# VGA_Breakout_Board.net
KiCad netlist of a schematic drawn in EAGLE
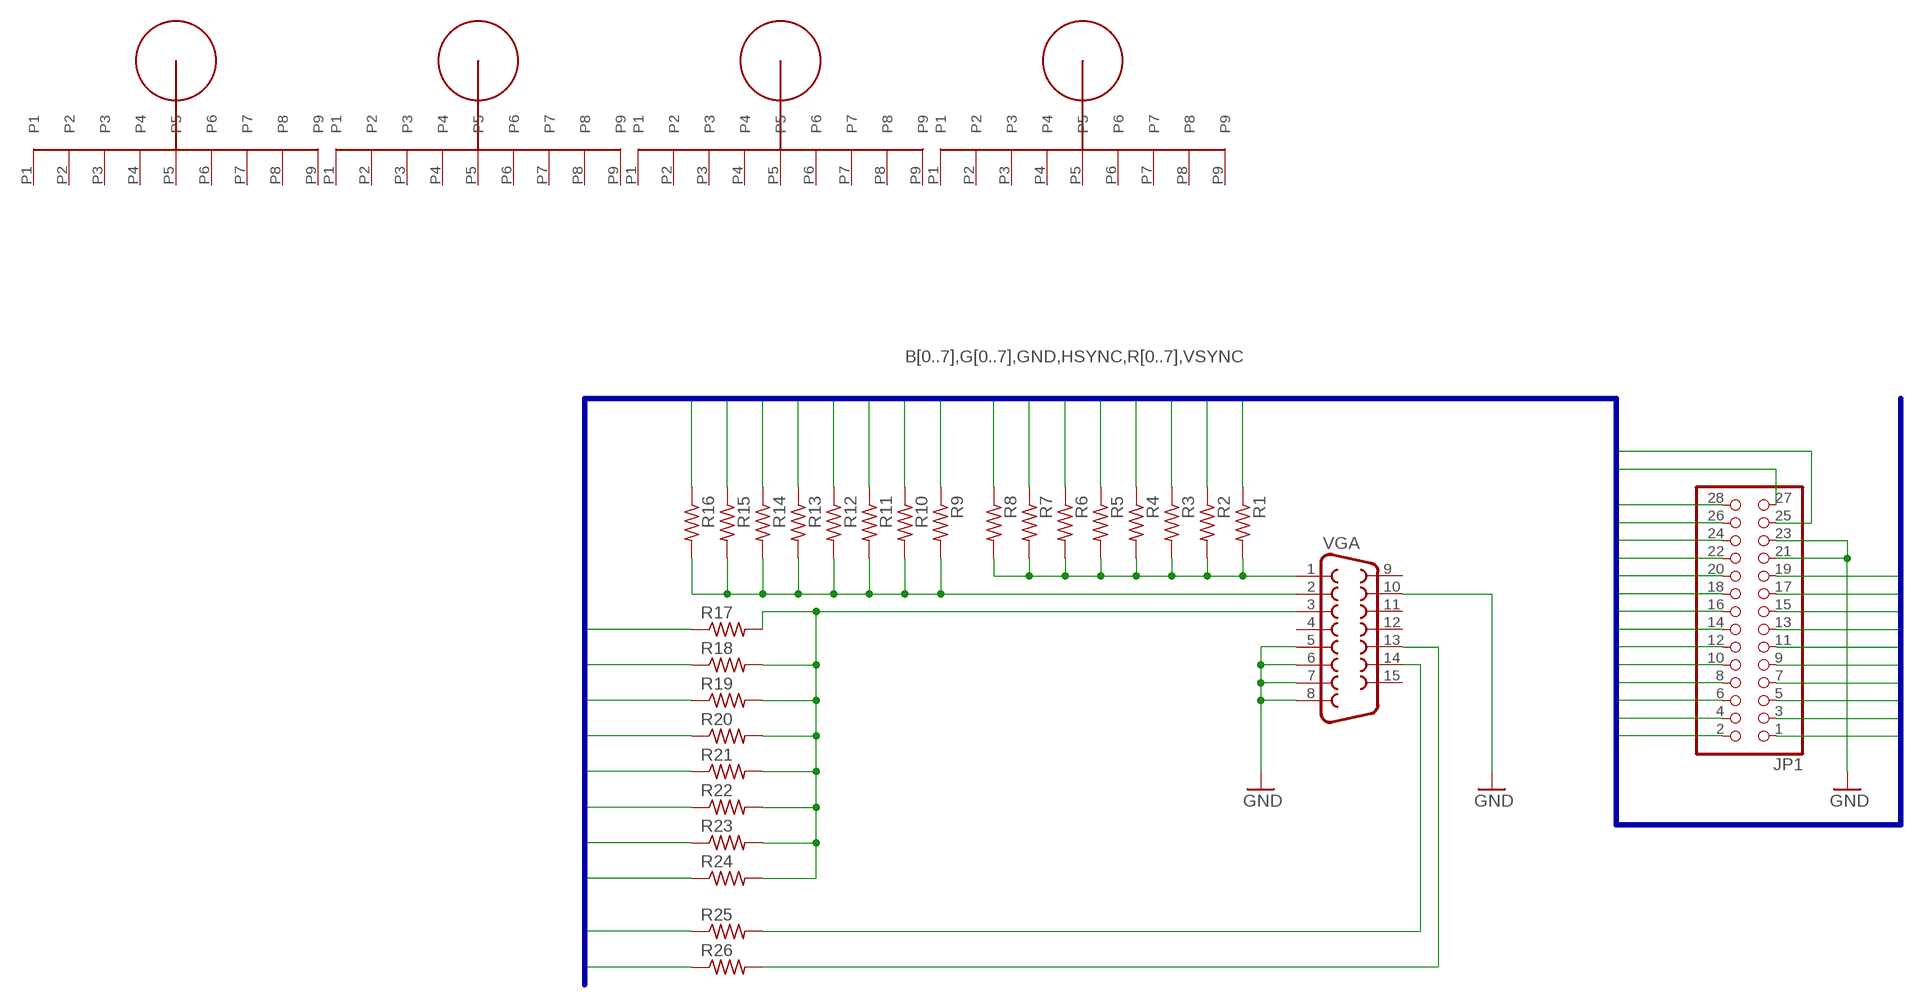
[diagram p0: schematic, sheet 1]

(export (version "E")
  (design (tool "Eeschema 10.0.6"))
  (components
    (comp (ref "JP1")
      (value "PINHD-2X14")
      (footprint "eagle-import:2X14")
      (libsource (lib "eagle-import") (part "PINHD-2X14"))
    )
    (comp (ref "R1")
      (value "R-US_0207/10")
      (footprint "eagle-import:0207_10")
      (libsource (lib "eagle-import") (part "R-US_0207/10"))
    )
    (comp (ref "R2")
      (value "R-US_0207/10")
      (footprint "eagle-import:0207_10")
      (libsource (lib "eagle-import") (part "R-US_0207/10"))
    )
    (comp (ref "R3")
      (value "R-US_0207/10")
      (footprint "eagle-import:0207_10")
      (libsource (lib "eagle-import") (part "R-US_0207/10"))
    )
    (comp (ref "R4")
      (value "R-US_0207/10")
      (footprint "eagle-import:0207_10")
      (libsource (lib "eagle-import") (part "R-US_0207/10"))
    )
    (comp (ref "R5")
      (value "R-US_0207/10")
      (footprint "eagle-import:0207_10")
      (libsource (lib "eagle-import") (part "R-US_0207/10"))
    )
    (comp (ref "R6")
      (value "R-US_0207/10")
      (footprint "eagle-import:0207_10")
      (libsource (lib "eagle-import") (part "R-US_0207/10"))
    )
    (comp (ref "R7")
      (value "R-US_0207/10")
      (footprint "eagle-import:0207_10")
      (libsource (lib "eagle-import") (part "R-US_0207/10"))
    )
    (comp (ref "R8")
      (value "R-US_0207/10")
      (footprint "eagle-import:0207_10")
      (libsource (lib "eagle-import") (part "R-US_0207/10"))
    )
    (comp (ref "R9")
      (value "R-US_0207/10")
      (footprint "eagle-import:0207_10")
      (libsource (lib "eagle-import") (part "R-US_0207/10"))
    )
    (comp (ref "R10")
      (value "R-US_0207/10")
      (footprint "eagle-import:0207_10")
      (libsource (lib "eagle-import") (part "R-US_0207/10"))
    )
    (comp (ref "R11")
      (value "R-US_0207/10")
      (footprint "eagle-import:0207_10")
      (libsource (lib "eagle-import") (part "R-US_0207/10"))
    )
    (comp (ref "R12")
      (value "R-US_0207/10")
      (footprint "eagle-import:0207_10")
      (libsource (lib "eagle-import") (part "R-US_0207/10"))
    )
    (comp (ref "R13")
      (value "R-US_0207/10")
      (footprint "eagle-import:0207_10")
      (libsource (lib "eagle-import") (part "R-US_0207/10"))
    )
    (comp (ref "R14")
      (value "R-US_0207/10")
      (footprint "eagle-import:0207_10")
      (libsource (lib "eagle-import") (part "R-US_0207/10"))
    )
    (comp (ref "R15")
      (value "R-US_0207/10")
      (footprint "eagle-import:0207_10")
      (libsource (lib "eagle-import") (part "R-US_0207/10"))
    )
    (comp (ref "R16")
      (value "R-US_0207/10")
      (footprint "eagle-import:0207_10")
      (libsource (lib "eagle-import") (part "R-US_0207/10"))
    )
    (comp (ref "R17")
      (value "R-US_0207/10")
      (footprint "eagle-import:0207_10")
      (libsource (lib "eagle-import") (part "R-US_0207/10"))
    )
    (comp (ref "R18")
      (value "R-US_0207/10")
      (footprint "eagle-import:0207_10")
      (libsource (lib "eagle-import") (part "R-US_0207/10"))
    )
    (comp (ref "R19")
      (value "R-US_0207/10")
      (footprint "eagle-import:0207_10")
      (libsource (lib "eagle-import") (part "R-US_0207/10"))
    )
    (comp (ref "R20")
      (value "R-US_0207/10")
      (footprint "eagle-import:0207_10")
      (libsource (lib "eagle-import") (part "R-US_0207/10"))
    )
    (comp (ref "R21")
      (value "R-US_0207/10")
      (footprint "eagle-import:0207_10")
      (libsource (lib "eagle-import") (part "R-US_0207/10"))
    )
    (comp (ref "R22")
      (value "R-US_0207/10")
      (footprint "eagle-import:0207_10")
      (libsource (lib "eagle-import") (part "R-US_0207/10"))
    )
    (comp (ref "R23")
      (value "R-US_0207/10")
      (footprint "eagle-import:0207_10")
      (libsource (lib "eagle-import") (part "R-US_0207/10"))
    )
    (comp (ref "R24")
      (value "R-US_0207/10")
      (footprint "eagle-import:0207_10")
      (libsource (lib "eagle-import") (part "R-US_0207/10"))
    )
    (comp (ref "R25")
      (value "R-US_0207/10")
      (footprint "eagle-import:0207_10")
      (libsource (lib "eagle-import") (part "R-US_0207/10"))
    )
    (comp (ref "R26")
      (value "R-US_0207/10")
      (footprint "eagle-import:0207_10")
      (libsource (lib "eagle-import") (part "R-US_0207/10"))
    )
    (comp (ref "U$1")
      (value "STANDOFF")
      (footprint "eagle-import:STANDOFF")
      (libsource (lib "eagle-import") (part "STANDOFF"))
    )
    (comp (ref "U$2")
      (value "STANDOFF")
      (footprint "eagle-import:STANDOFF")
      (libsource (lib "eagle-import") (part "STANDOFF"))
    )
    (comp (ref "U$3")
      (value "STANDOFF")
      (footprint "eagle-import:STANDOFF")
      (libsource (lib "eagle-import") (part "STANDOFF"))
    )
    (comp (ref "U$4")
      (value "STANDOFF")
      (footprint "eagle-import:STANDOFF")
      (libsource (lib "eagle-import") (part "STANDOFF"))
    )
    (comp (ref "VGA")
      (value "F15HDH")
      (footprint "eagle-import:HDF15H")
      (libsource (lib "eagle-import") (part "F15HDH"))
    )
  )
  (nets
    (net (code "1") (name "/B0") (class "Default")
      (node (ref "JP1") (pin "18") (pinfunction "18_18") (pintype "passive"))
      (node (ref "R17") (pin "1") (pinfunction "1_1") (pintype "passive"))
    )
    (net (code "2") (name "/B1") (class "Default")
      (node (ref "JP1") (pin "20") (pinfunction "20_20") (pintype "passive"))
      (node (ref "R18") (pin "1") (pinfunction "1_1") (pintype "passive"))
    )
    (net (code "3") (name "/B2") (class "Default")
      (node (ref "JP1") (pin "22") (pinfunction "22_22") (pintype "passive"))
      (node (ref "R19") (pin "1") (pinfunction "1_1") (pintype "passive"))
    )
    (net (code "4") (name "/B3") (class "Default")
      (node (ref "JP1") (pin "24") (pinfunction "24_24") (pintype "passive"))
      (node (ref "R20") (pin "1") (pinfunction "1_1") (pintype "passive"))
    )
    (net (code "5") (name "/B4") (class "Default")
      (node (ref "JP1") (pin "26") (pinfunction "26_26") (pintype "passive"))
      (node (ref "R21") (pin "1") (pinfunction "1_1") (pintype "passive"))
    )
    (net (code "6") (name "/B5") (class "Default")
      (node (ref "JP1") (pin "28") (pinfunction "28_28") (pintype "passive"))
      (node (ref "R22") (pin "1") (pinfunction "1_1") (pintype "passive"))
    )
    (net (code "7") (name "/B6") (class "Default")
      (node (ref "JP1") (pin "27") (pinfunction "27_27") (pintype "passive"))
      (node (ref "R23") (pin "1") (pinfunction "1_1") (pintype "passive"))
    )
    (net (code "8") (name "/B7") (class "Default")
      (node (ref "JP1") (pin "25") (pinfunction "25_25") (pintype "passive"))
      (node (ref "R24") (pin "1") (pinfunction "1_1") (pintype "passive"))
    )
    (net (code "9") (name "/G0") (class "Default")
      (node (ref "JP1") (pin "1") (pinfunction "1_1") (pintype "passive"))
      (node (ref "R9") (pin "1") (pinfunction "1_1") (pintype "passive"))
    )
    (net (code "10") (name "/G1") (class "Default")
      (node (ref "JP1") (pin "3") (pinfunction "3_3") (pintype "passive"))
      (node (ref "R10") (pin "1") (pinfunction "1_1") (pintype "passive"))
    )
    (net (code "11") (name "/G2") (class "Default")
      (node (ref "JP1") (pin "5") (pinfunction "5_5") (pintype "passive"))
      (node (ref "R11") (pin "1") (pinfunction "1_1") (pintype "passive"))
    )
    (net (code "12") (name "/G3") (class "Default")
      (node (ref "JP1") (pin "7") (pinfunction "7_7") (pintype "passive"))
      (node (ref "R12") (pin "1") (pinfunction "1_1") (pintype "passive"))
    )
    (net (code "13") (name "/G4") (class "Default")
      (node (ref "JP1") (pin "9") (pinfunction "9_9") (pintype "passive"))
      (node (ref "R13") (pin "1") (pinfunction "1_1") (pintype "passive"))
    )
    (net (code "14") (name "/G5") (class "Default")
      (node (ref "JP1") (pin "11") (pinfunction "11_11") (pintype "passive"))
      (node (ref "R14") (pin "1") (pinfunction "1_1") (pintype "passive"))
    )
    (net (code "15") (name "/G6") (class "Default")
      (node (ref "JP1") (pin "13") (pinfunction "13_13") (pintype "passive"))
      (node (ref "R15") (pin "1") (pinfunction "1_1") (pintype "passive"))
    )
    (net (code "16") (name "/G7") (class "Default")
      (node (ref "JP1") (pin "15") (pinfunction "15_15") (pintype "passive"))
      (node (ref "R16") (pin "1") (pinfunction "1_1") (pintype "passive"))
    )
    (net (code "17") (name "/HSYNC") (class "Default")
      (node (ref "JP1") (pin "17") (pinfunction "17_17") (pintype "passive"))
      (node (ref "R26") (pin "1") (pinfunction "1_1") (pintype "passive"))
    )
    (net (code "18") (name "/R0") (class "Default")
      (node (ref "JP1") (pin "16") (pinfunction "16_16") (pintype "passive"))
      (node (ref "R1") (pin "1") (pinfunction "1_1") (pintype "passive"))
    )
    (net (code "19") (name "/R1") (class "Default")
      (node (ref "JP1") (pin "14") (pinfunction "14_14") (pintype "passive"))
      (node (ref "R2") (pin "1") (pinfunction "1_1") (pintype "passive"))
    )
    (net (code "20") (name "/R2") (class "Default")
      (node (ref "JP1") (pin "12") (pinfunction "12_12") (pintype "passive"))
      (node (ref "R3") (pin "1") (pinfunction "1_1") (pintype "passive"))
    )
    (net (code "21") (name "/R3") (class "Default")
      (node (ref "JP1") (pin "10") (pinfunction "10_10") (pintype "passive"))
      (node (ref "R4") (pin "1") (pinfunction "1_1") (pintype "passive"))
    )
    (net (code "22") (name "/R4") (class "Default")
      (node (ref "JP1") (pin "8") (pinfunction "8_8") (pintype "passive"))
      (node (ref "R5") (pin "1") (pinfunction "1_1") (pintype "passive"))
    )
    (net (code "23") (name "/R5") (class "Default")
      (node (ref "JP1") (pin "6") (pinfunction "6_6") (pintype "passive"))
      (node (ref "R6") (pin "1") (pinfunction "1_1") (pintype "passive"))
    )
    (net (code "24") (name "/R6") (class "Default")
      (node (ref "JP1") (pin "4") (pinfunction "4_4") (pintype "passive"))
      (node (ref "R7") (pin "1") (pinfunction "1_1") (pintype "passive"))
    )
    (net (code "25") (name "/R7") (class "Default")
      (node (ref "JP1") (pin "2") (pinfunction "2_2") (pintype "passive"))
      (node (ref "R8") (pin "1") (pinfunction "1_1") (pintype "passive"))
    )
    (net (code "26") (name "/VSYNC") (class "Default")
      (node (ref "JP1") (pin "19") (pinfunction "19_19") (pintype "passive"))
      (node (ref "R25") (pin "1") (pinfunction "1_1") (pintype "passive"))
    )
    (net (code "28") (name "GND") (class "Default")
      (node (ref "JP1") (pin "21") (pinfunction "21_21") (pintype "passive"))
      (node (ref "JP1") (pin "23") (pinfunction "23_23") (pintype "passive"))
      (node (ref "VGA") (pin "10") (pinfunction "10_10") (pintype "passive"))
      (node (ref "VGA") (pin "5") (pinfunction "5_5") (pintype "passive"))
      (node (ref "VGA") (pin "6") (pinfunction "6_6") (pintype "passive"))
      (node (ref "VGA") (pin "7") (pinfunction "7_7") (pintype "passive"))
      (node (ref "VGA") (pin "8") (pinfunction "8_8") (pintype "passive"))
    )
    (net (code "29") (name "Net-(R1-Pad2)") (class "Default")
      (node (ref "R1") (pin "2") (pinfunction "2_2") (pintype "passive"))
      (node (ref "R2") (pin "2") (pinfunction "2_2") (pintype "passive"))
      (node (ref "R3") (pin "2") (pinfunction "2_2") (pintype "passive"))
      (node (ref "R4") (pin "2") (pinfunction "2_2") (pintype "passive"))
      (node (ref "R5") (pin "2") (pinfunction "2_2") (pintype "passive"))
      (node (ref "R6") (pin "2") (pinfunction "2_2") (pintype "passive"))
      (node (ref "R7") (pin "2") (pinfunction "2_2") (pintype "passive"))
      (node (ref "R8") (pin "2") (pinfunction "2_2") (pintype "passive"))
      (node (ref "VGA") (pin "1") (pinfunction "1_1") (pintype "passive"))
    )
    (net (code "30") (name "Net-(R10-Pad2)") (class "Default")
      (node (ref "R10") (pin "2") (pinfunction "2_2") (pintype "passive"))
      (node (ref "R11") (pin "2") (pinfunction "2_2") (pintype "passive"))
      (node (ref "R12") (pin "2") (pinfunction "2_2") (pintype "passive"))
      (node (ref "R13") (pin "2") (pinfunction "2_2") (pintype "passive"))
      (node (ref "R14") (pin "2") (pinfunction "2_2") (pintype "passive"))
      (node (ref "R15") (pin "2") (pinfunction "2_2") (pintype "passive"))
      (node (ref "R16") (pin "2") (pinfunction "2_2") (pintype "passive"))
      (node (ref "R9") (pin "2") (pinfunction "2_2") (pintype "passive"))
      (node (ref "VGA") (pin "2") (pinfunction "2_2") (pintype "passive"))
    )
    (net (code "31") (name "Net-(R17-Pad2)") (class "Default")
      (node (ref "R17") (pin "2") (pinfunction "2_2") (pintype "passive"))
      (node (ref "R18") (pin "2") (pinfunction "2_2") (pintype "passive"))
      (node (ref "R19") (pin "2") (pinfunction "2_2") (pintype "passive"))
      (node (ref "R20") (pin "2") (pinfunction "2_2") (pintype "passive"))
      (node (ref "R21") (pin "2") (pinfunction "2_2") (pintype "passive"))
      (node (ref "R22") (pin "2") (pinfunction "2_2") (pintype "passive"))
      (node (ref "R23") (pin "2") (pinfunction "2_2") (pintype "passive"))
      (node (ref "R24") (pin "2") (pinfunction "2_2") (pintype "passive"))
      (node (ref "VGA") (pin "3") (pinfunction "3_3") (pintype "passive"))
    )
    (net (code "32") (name "Net-(R25-Pad2)") (class "Default")
      (node (ref "R25") (pin "2") (pinfunction "2_2") (pintype "passive"))
      (node (ref "VGA") (pin "14") (pinfunction "14_14") (pintype "passive"))
    )
    (net (code "33") (name "Net-(R26-Pad2)") (class "Default")
      (node (ref "R26") (pin "2") (pinfunction "2_2") (pintype "passive"))
      (node (ref "VGA") (pin "13") (pinfunction "13_13") (pintype "passive"))
    )
    (net (code "34") (name "unconnected-(U$1-PadP1)") (class "Default")
      (node (ref "U$1") (pin "P1") (pinfunction "P1_P1") (pintype "bidirectional"))
    )
    (net (code "35") (name "unconnected-(U$1-PadP2)") (class "Default")
      (node (ref "U$1") (pin "P2") (pinfunction "P2_P2") (pintype "bidirectional"))
    )
    (net (code "36") (name "unconnected-(U$1-PadP3)") (class "Default")
      (node (ref "U$1") (pin "P3") (pinfunction "P3_P3") (pintype "bidirectional"))
    )
    (net (code "37") (name "unconnected-(U$1-PadP4)") (class "Default")
      (node (ref "U$1") (pin "P4") (pinfunction "P4_P4") (pintype "bidirectional"))
    )
    (net (code "38") (name "unconnected-(U$1-PadP5)") (class "Default")
      (node (ref "U$1") (pin "P5") (pinfunction "P5_P5") (pintype "bidirectional"))
    )
    (net (code "39") (name "unconnected-(U$1-PadP6)") (class "Default")
      (node (ref "U$1") (pin "P6") (pinfunction "P6_P6") (pintype "bidirectional"))
    )
    (net (code "40") (name "unconnected-(U$1-PadP7)") (class "Default")
      (node (ref "U$1") (pin "P7") (pinfunction "P7_P7") (pintype "bidirectional"))
    )
    (net (code "41") (name "unconnected-(U$1-PadP8)") (class "Default")
      (node (ref "U$1") (pin "P8") (pinfunction "P8_P8") (pintype "bidirectional"))
    )
    (net (code "42") (name "unconnected-(U$1-PadP9)") (class "Default")
      (node (ref "U$1") (pin "P9") (pinfunction "P9_P9") (pintype "bidirectional"))
    )
    (net (code "43") (name "unconnected-(U$2-PadP1)") (class "Default")
      (node (ref "U$2") (pin "P1") (pinfunction "P1_P1") (pintype "bidirectional"))
    )
    (net (code "44") (name "unconnected-(U$2-PadP2)") (class "Default")
      (node (ref "U$2") (pin "P2") (pinfunction "P2_P2") (pintype "bidirectional"))
    )
    (net (code "45") (name "unconnected-(U$2-PadP3)") (class "Default")
      (node (ref "U$2") (pin "P3") (pinfunction "P3_P3") (pintype "bidirectional"))
    )
    (net (code "46") (name "unconnected-(U$2-PadP4)") (class "Default")
      (node (ref "U$2") (pin "P4") (pinfunction "P4_P4") (pintype "bidirectional"))
    )
    (net (code "47") (name "unconnected-(U$2-PadP5)") (class "Default")
      (node (ref "U$2") (pin "P5") (pinfunction "P5_P5") (pintype "bidirectional"))
    )
    (net (code "48") (name "unconnected-(U$2-PadP6)") (class "Default")
      (node (ref "U$2") (pin "P6") (pinfunction "P6_P6") (pintype "bidirectional"))
    )
    (net (code "49") (name "unconnected-(U$2-PadP7)") (class "Default")
      (node (ref "U$2") (pin "P7") (pinfunction "P7_P7") (pintype "bidirectional"))
    )
    (net (code "50") (name "unconnected-(U$2-PadP8)") (class "Default")
      (node (ref "U$2") (pin "P8") (pinfunction "P8_P8") (pintype "bidirectional"))
    )
    (net (code "51") (name "unconnected-(U$2-PadP9)") (class "Default")
      (node (ref "U$2") (pin "P9") (pinfunction "P9_P9") (pintype "bidirectional"))
    )
    (net (code "52") (name "unconnected-(U$3-PadP1)") (class "Default")
      (node (ref "U$3") (pin "P1") (pinfunction "P1_P1") (pintype "bidirectional"))
    )
    (net (code "53") (name "unconnected-(U$3-PadP2)") (class "Default")
      (node (ref "U$3") (pin "P2") (pinfunction "P2_P2") (pintype "bidirectional"))
    )
    (net (code "54") (name "unconnected-(U$3-PadP3)") (class "Default")
      (node (ref "U$3") (pin "P3") (pinfunction "P3_P3") (pintype "bidirectional"))
    )
    (net (code "55") (name "unconnected-(U$3-PadP4)") (class "Default")
      (node (ref "U$3") (pin "P4") (pinfunction "P4_P4") (pintype "bidirectional"))
    )
    (net (code "56") (name "unconnected-(U$3-PadP5)") (class "Default")
      (node (ref "U$3") (pin "P5") (pinfunction "P5_P5") (pintype "bidirectional"))
    )
    (net (code "57") (name "unconnected-(U$3-PadP6)") (class "Default")
      (node (ref "U$3") (pin "P6") (pinfunction "P6_P6") (pintype "bidirectional"))
    )
    (net (code "58") (name "unconnected-(U$3-PadP7)") (class "Default")
      (node (ref "U$3") (pin "P7") (pinfunction "P7_P7") (pintype "bidirectional"))
    )
    (net (code "59") (name "unconnected-(U$3-PadP8)") (class "Default")
      (node (ref "U$3") (pin "P8") (pinfunction "P8_P8") (pintype "bidirectional"))
    )
    (net (code "60") (name "unconnected-(U$3-PadP9)") (class "Default")
      (node (ref "U$3") (pin "P9") (pinfunction "P9_P9") (pintype "bidirectional"))
    )
    (net (code "61") (name "unconnected-(U$4-PadP1)") (class "Default")
      (node (ref "U$4") (pin "P1") (pinfunction "P1_P1") (pintype "bidirectional"))
    )
    (net (code "62") (name "unconnected-(U$4-PadP2)") (class "Default")
      (node (ref "U$4") (pin "P2") (pinfunction "P2_P2") (pintype "bidirectional"))
    )
    (net (code "63") (name "unconnected-(U$4-PadP3)") (class "Default")
      (node (ref "U$4") (pin "P3") (pinfunction "P3_P3") (pintype "bidirectional"))
    )
    (net (code "64") (name "unconnected-(U$4-PadP4)") (class "Default")
      (node (ref "U$4") (pin "P4") (pinfunction "P4_P4") (pintype "bidirectional"))
    )
    (net (code "65") (name "unconnected-(U$4-PadP5)") (class "Default")
      (node (ref "U$4") (pin "P5") (pinfunction "P5_P5") (pintype "bidirectional"))
    )
    (net (code "66") (name "unconnected-(U$4-PadP6)") (class "Default")
      (node (ref "U$4") (pin "P6") (pinfunction "P6_P6") (pintype "bidirectional"))
    )
    (net (code "67") (name "unconnected-(U$4-PadP7)") (class "Default")
      (node (ref "U$4") (pin "P7") (pinfunction "P7_P7") (pintype "bidirectional"))
    )
    (net (code "68") (name "unconnected-(U$4-PadP8)") (class "Default")
      (node (ref "U$4") (pin "P8") (pinfunction "P8_P8") (pintype "bidirectional"))
    )
    (net (code "69") (name "unconnected-(U$4-PadP9)") (class "Default")
      (node (ref "U$4") (pin "P9") (pinfunction "P9_P9") (pintype "bidirectional"))
    )
    (net (code "70") (name "unconnected-(VGA-Pad4)") (class "Default")
      (node (ref "VGA") (pin "4") (pinfunction "4_4") (pintype "passive"))
    )
    (net (code "71") (name "unconnected-(VGA-Pad9)") (class "Default")
      (node (ref "VGA") (pin "9") (pinfunction "9_9") (pintype "passive"))
    )
    (net (code "72") (name "unconnected-(VGA-Pad11)") (class "Default")
      (node (ref "VGA") (pin "11") (pinfunction "11_11") (pintype "passive"))
    )
    (net (code "73") (name "unconnected-(VGA-Pad12)") (class "Default")
      (node (ref "VGA") (pin "12") (pinfunction "12_12") (pintype "passive"))
    )
    (net (code "74") (name "unconnected-(VGA-Pad15)") (class "Default")
      (node (ref "VGA") (pin "15") (pinfunction "15_15") (pintype "passive"))
    )
  )
)
